# Enclosure_100x68_BHWL.net
KiCad netlist of a schematic drawn in EAGLE
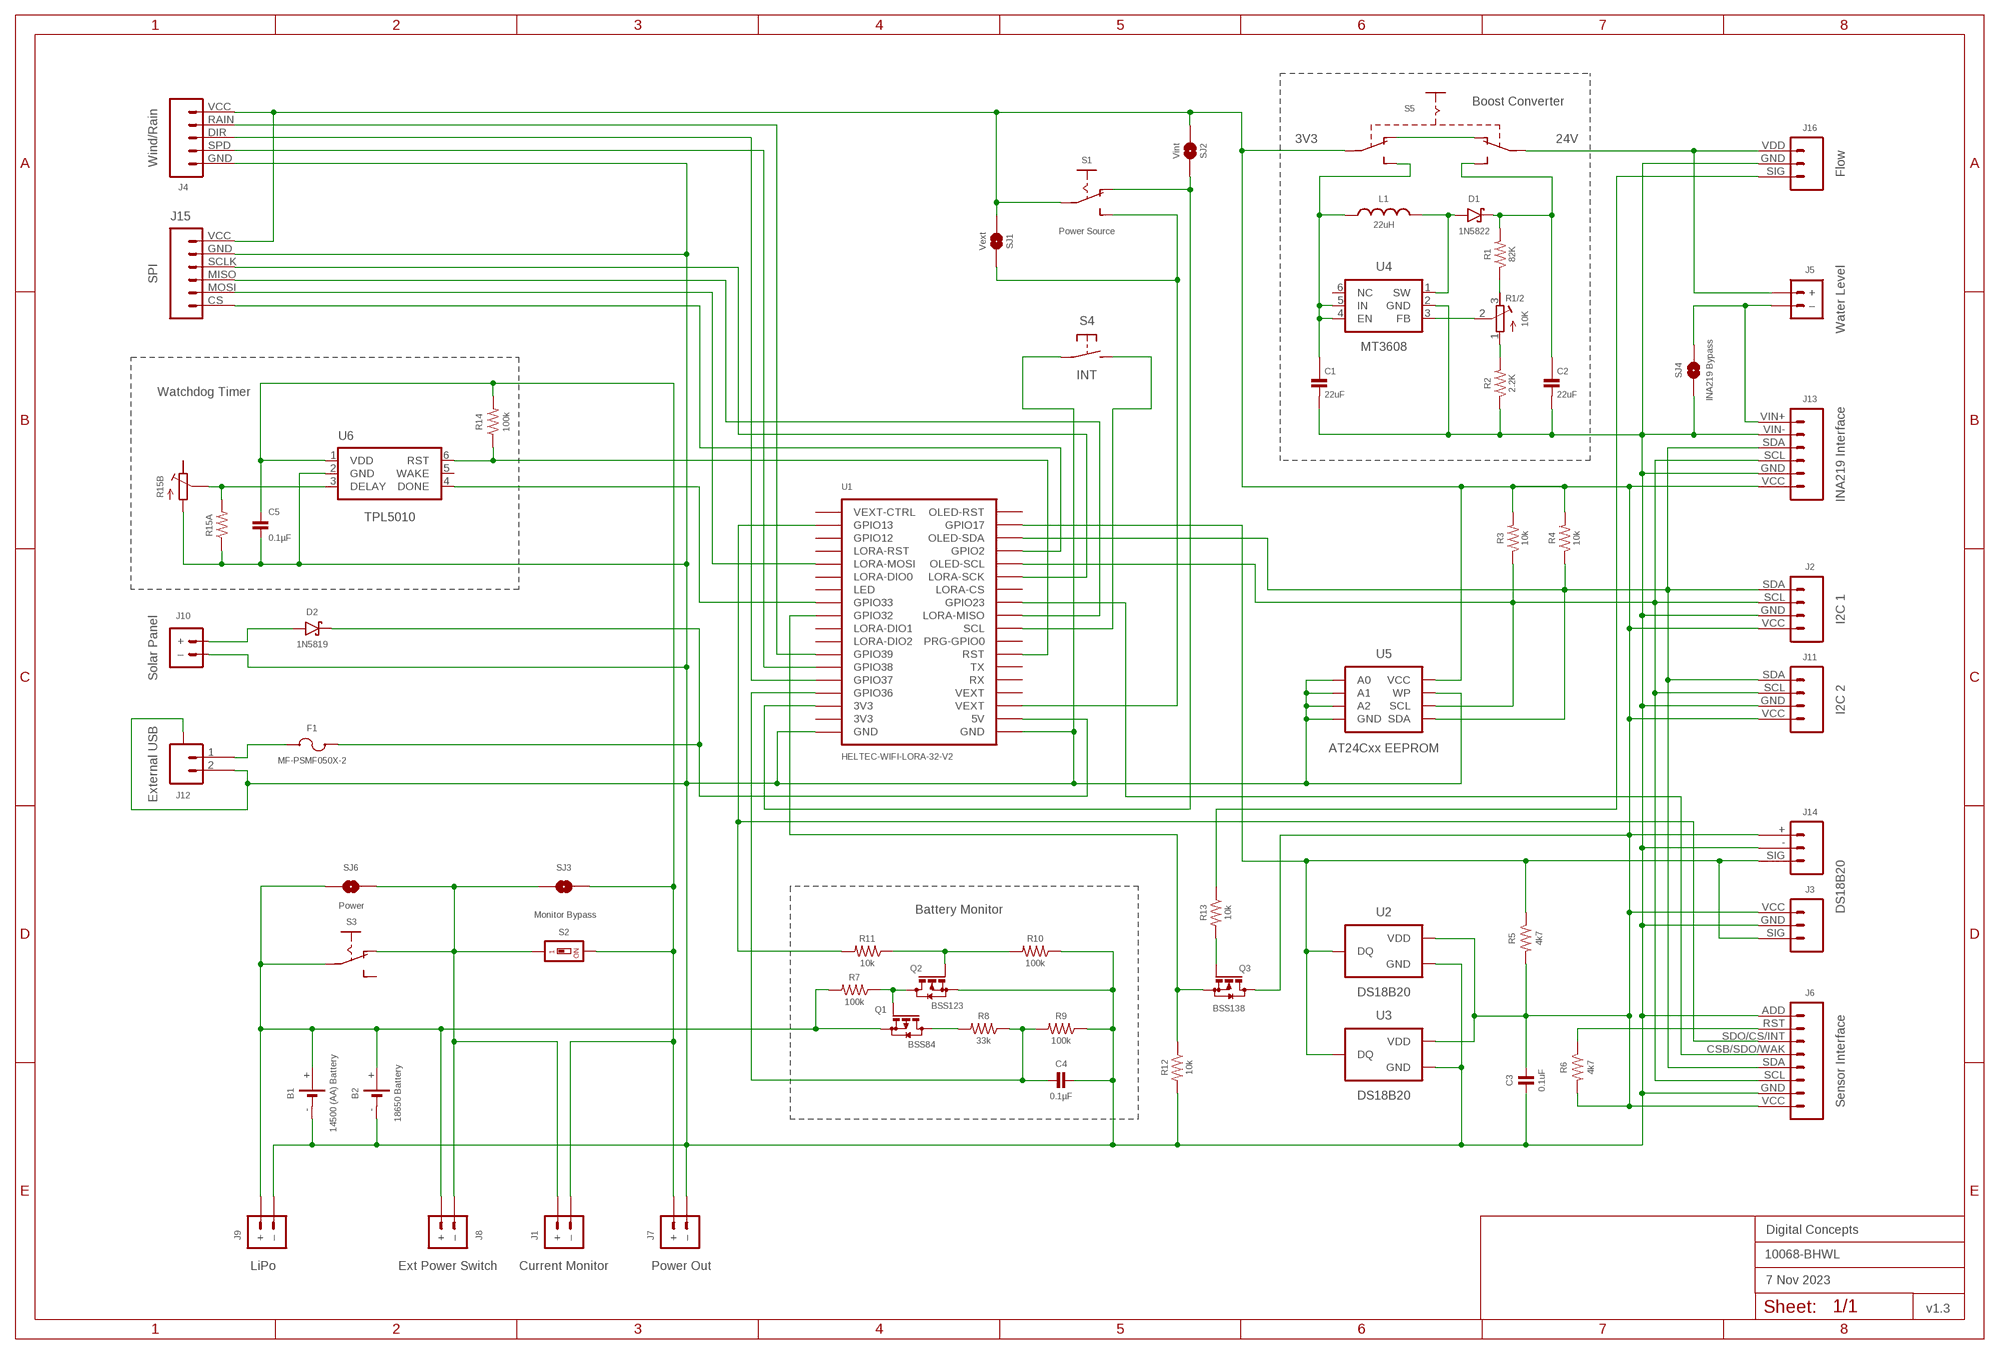
[diagram p0: schematic, sheet 1]

(export (version "E")
  (design (tool "Eeschema 10.0.6"))
  (components
    (comp (ref "B1")
      (value "14500 (AA) Battery")
      (footprint "eagle-import:BATTERY-14500")
      (libsource (lib "eagle-import") (part "BATTERY-HOLDER-14500(AA)"))
    )
    (comp (ref "B2")
      (value "18650 Battery")
      (footprint "eagle-import:BATTERY-18650")
      (libsource (lib "eagle-import") (part "BATTERY-HOLDER-18650"))
    )
    (comp (ref "C1")
      (value "22uF")
      (footprint "eagle-import:C1206")
      (libsource (lib "eagle-import") (part "CAPACITOR-1206"))
    )
    (comp (ref "C2")
      (value "22uF")
      (footprint "eagle-import:C1206")
      (libsource (lib "eagle-import") (part "CAPACITOR-1206"))
    )
    (comp (ref "C3")
      (value "0.1uF")
      (footprint "eagle-import:C0805")
      (libsource (lib "eagle-import") (part "CAPACITOR-0805"))
    )
    (comp (ref "C4")
      (value "0.1µF")
      (footprint "eagle-import:C0805")
      (libsource (lib "eagle-import") (part "CAPACITOR-0805"))
    )
    (comp (ref "C5")
      (value "0.1µF")
      (footprint "eagle-import:C0805")
      (libsource (lib "eagle-import") (part "CAPACITOR-0805"))
    )
    (comp (ref "D1")
      (value "1N5822")
      (footprint "eagle-import:DIODE_SMB")
      (libsource (lib "eagle-import") (part "DIODE-SCHOTTKY-1N5822"))
    )
    (comp (ref "D2")
      (value "1N5819")
      (footprint "eagle-import:SOD-123")
      (libsource (lib "eagle-import") (part "1N5819-SOD-123"))
    )
    (comp (ref "F1")
      (value "MF-PSMF050X-2")
      (footprint "eagle-import:F0805")
      (libsource (lib "eagle-import") (part "MF-PSMF050X-2"))
    )
    (comp (ref "J1")
      (value "Current Monitor")
      (footprint "eagle-import:JST-PH2.0-2-HORIZONTAL")
      (libsource (lib "eagle-import") (part "JST-PH2.0-2-HORIZONTALJST-PTH-2"))
    )
    (comp (ref "J2")
      (value "I2C 1")
      (footprint "eagle-import:JST-PH2.0-4-VERTICAL-I2C")
      (libsource (lib "eagle-import") (part "JST-PH2.0-4-VERTICAL-I2C"))
    )
    (comp (ref "J3")
      (value "DS18B20")
      (footprint "eagle-import:JST-PH2.0-3-VERTICAL-SIG")
      (libsource (lib "eagle-import") (part "JST-PH2.0-3-VERTICAL-DS18B20"))
    )
    (comp (ref "J4")
      (value "Wind/Rain")
      (footprint "eagle-import:JST-PH2.0-5-DUAL-WEATHER")
      (libsource (lib "eagle-import") (part "JST-PH2.0-5-DUAL-WEATHER"))
    )
    (comp (ref "J5")
      (value "Water Level")
      (footprint "eagle-import:JST-PH2.0-2-DUAL-POWER")
      (libsource (lib "eagle-import") (part "JST-PH2.0-2-DUAL-POWERJST-PTH-2"))
    )
    (comp (ref "J6")
      (value "Sensor Interface")
      (footprint "eagle-import:CONN_08-SENSOR")
      (libsource (lib "eagle-import") (part "HEADER-1X8-SENSOR"))
    )
    (comp (ref "J7")
      (value "Power Out")
      (footprint "eagle-import:JST-GH1.25-2-HORIZONTAL")
      (libsource (lib "eagle-import") (part "JST-GH1.25-2-HORIZONTAL-POWER"))
    )
    (comp (ref "J8")
      (value "Ext Power Switch")
      (footprint "eagle-import:JST-PH2.0-2-DUAL-POWER")
      (libsource (lib "eagle-import") (part "JST-PH2.0-2-DUAL-POWERJST-PTH-2"))
    )
    (comp (ref "J9")
      (value "LiPo")
      (footprint "eagle-import:JST-PH2.0-2-HORIZONTAL-POWER")
      (libsource (lib "eagle-import") (part "JST-PH2.0-2-HORIZONTAL-POWERJST-PTH-2"))
    )
    (comp (ref "J10")
      (value "Solar Panel")
      (footprint "eagle-import:JST-PH2.0-2-VERTICAL=POWER")
      (libsource (lib "eagle-import") (part "JST-PH2.0-2-VERTICAL"))
    )
    (comp (ref "J11")
      (value "I2C 2")
      (footprint "eagle-import:JST-PH2.0-4-HORIZONTAL")
      (libsource (lib "eagle-import") (part "JST-PH2.0-I2C-MALE-HORIZONTAL"))
    )
    (comp (ref "J12")
      (value "External USB")
      (footprint "eagle-import:JST-SH1.0-2-HORIZONTAL")
      (libsource (lib "eagle-import") (part "JST-SH1.0-2-SMD-HORIZONTAL"))
    )
    (comp (ref "J13")
      (value "INA219 Interface")
      (footprint "eagle-import:CONN_06-INA219")
      (libsource (lib "eagle-import") (part "INA219-I2C-MODULE"))
    )
    (comp (ref "J14")
      (value "JST-PH2.0-3-HORIZONTAL-DS18B20")
      (footprint "eagle-import:JST-PH2.0-3-HORIZONTAL-DS18B20")
      (libsource (lib "eagle-import") (part "JST-PH2.0-3-HORIZONTAL-DS18B20"))
    )
    (comp (ref "J15")
      (value "SPI")
      (footprint "eagle-import:JST-PH2.0-6-HORIZONTAL-SPI")
      (libsource (lib "eagle-import") (part "JST-PH2.0-6-HORIZONTAL-SPI"))
    )
    (comp (ref "J16")
      (value "Flow")
      (footprint "eagle-import:JST-XH2.4-3-VERTICAL-SENSOR")
      (libsource (lib "eagle-import") (part "JST-XH2.54-3-VERTICAL-SENSOR"))
    )
    (comp (ref "L1")
      (value "22uH")
      (footprint "eagle-import:CDRH104R+6D28")
      (libsource (lib "eagle-import") (part "INDUCTOR-CDRH104R/6D28L5038P"))
    )
    (comp (ref "Q1")
      (value "BSS84")
      (footprint "eagle-import:SOT23-3")
      (libsource (lib "eagle-import") (part "BSS84"))
    )
    (comp (ref "Q2")
      (value "BSS123")
      (footprint "eagle-import:SOT23-3")
      (libsource (lib "eagle-import") (part "MOSFET-BSS123"))
    )
    (comp (ref "Q3")
      (value "BSS138")
      (footprint "eagle-import:SOT23-3")
      (libsource (lib "eagle-import") (part "MOSFET-BSS123"))
    )
    (comp (ref "R1")
      (value "82K")
      (footprint "eagle-import:R0805")
      (libsource (lib "eagle-import") (part "RESISTORR0805"))
    )
    (comp (ref "R1/2")
      (value "10K")
      (footprint "eagle-import:RTRIM64P")
      (libsource (lib "eagle-import") (part "RESISTOR-TRIMM-BAOTER-HORIZONTAL"))
    )
    (comp (ref "R2")
      (value "2.2K")
      (footprint "eagle-import:R0805")
      (libsource (lib "eagle-import") (part "RESISTORR0805"))
    )
    (comp (ref "R3")
      (value "10k")
      (footprint "eagle-import:R0805")
      (libsource (lib "eagle-import") (part "RESISTORR0805"))
    )
    (comp (ref "R4")
      (value "10k")
      (footprint "eagle-import:R0805")
      (libsource (lib "eagle-import") (part "RESISTORR0805"))
    )
    (comp (ref "R5")
      (value "4k7")
      (footprint "eagle-import:R0805")
      (libsource (lib "eagle-import") (part "RESISTORR0805"))
    )
    (comp (ref "R6")
      (value "4k7")
      (footprint "eagle-import:R0805")
      (libsource (lib "eagle-import") (part "RESISTORR0805"))
    )
    (comp (ref "R7")
      (value "100k")
      (footprint "eagle-import:R0805")
      (libsource (lib "eagle-import") (part "RESISTORR0805"))
    )
    (comp (ref "R8")
      (value "33k")
      (footprint "eagle-import:R0805")
      (libsource (lib "eagle-import") (part "RESISTORR0805"))
    )
    (comp (ref "R9")
      (value "100k")
      (footprint "eagle-import:R0805")
      (libsource (lib "eagle-import") (part "RESISTORR0805"))
    )
    (comp (ref "R10")
      (value "100k")
      (footprint "eagle-import:R0805")
      (libsource (lib "eagle-import") (part "RESISTORR0805"))
    )
    (comp (ref "R11")
      (value "10k")
      (footprint "eagle-import:R0805")
      (libsource (lib "eagle-import") (part "RESISTORR0805"))
    )
    (comp (ref "R12")
      (value "10k")
      (footprint "eagle-import:R0805")
      (libsource (lib "eagle-import") (part "RESISTORR0805"))
    )
    (comp (ref "R13")
      (value "10k")
      (footprint "eagle-import:R0805")
      (libsource (lib "eagle-import") (part "RESISTORR0805"))
    )
    (comp (ref "R14")
      (value "100k")
      (footprint "eagle-import:R0805")
      (libsource (lib "eagle-import") (part "RESISTORR0805"))
    )
    (comp (ref "R15A")
      (value "RESISTORR0805")
      (footprint "eagle-import:R0805")
      (libsource (lib "eagle-import") (part "RESISTORR0805"))
    )
    (comp (ref "R15B")
      (value "RESISTOR-TRIMM-33")
      (footprint "eagle-import:RTRIM3_3")
      (libsource (lib "eagle-import") (part "RESISTOR-TRIMM-33"))
    )
    (comp (ref "S1")
      (value "Power Source")
      (footprint "eagle-import:SWITCH-SPDT-SMT")
      (libsource (lib "eagle-import") (part "SWITCH-SLIDE-SPDT-SMT"))
    )
    (comp (ref "S2")
      (value "Monitor Bypass")
      (footprint "eagle-import:SMD-001")
      (libsource (lib "eagle-import") (part "SWITCH-DIP-SWS001"))
    )
    (comp (ref "S3")
      (value "Power")
      (footprint "eagle-import:SWITCH-SPDT-PTH")
      (libsource (lib "eagle-import") (part "SWITCH-SLIDE-SPDT-PTH"))
    )
    (comp (ref "S4")
      (value "INT")
      (footprint "eagle-import:SWITCH-2-PAD")
      (libsource (lib "eagle-import") (part "SWITCH-MOMENTARY-2-PIN"))
    )
    (comp (ref "S5")
      (value "SWITCH-SLIDE-DPDT-PTH-S")
      (footprint "eagle-import:SWITCH-DPDT-PTH")
      (libsource (lib "eagle-import") (part "SWITCH-SLIDE-DPDT-PTH-S"))
    )
    (comp (ref "SJ1")
      (value "Vext")
      (footprint "eagle-import:SJ")
      (libsource (lib "eagle-import") (part "SJ"))
    )
    (comp (ref "SJ2")
      (value "Vint")
      (footprint "eagle-import:SJ-VIA-2")
      (libsource (lib "eagle-import") (part "SJ-V-2"))
    )
    (comp (ref "SJ3")
      (value "Monitor")
      (footprint "eagle-import:SJ")
      (libsource (lib "eagle-import") (part "SJ"))
    )
    (comp (ref "SJ4")
      (value "INA219 Bypass")
      (footprint "eagle-import:SJ")
      (libsource (lib "eagle-import") (part "SJ"))
    )
    (comp (ref "SJ6")
      (value "Power")
      (footprint "eagle-import:SJ")
      (libsource (lib "eagle-import") (part "SJ"))
    )
    (comp (ref "U1")
      (value "HELTEC-WIFI-LORA-32-V2")
      (footprint "eagle-import:HELTEC-WIFI-LORA-32-V2")
      (libsource (lib "eagle-import") (part "HELTEC-WIFI-LORA-32-V2"))
    )
    (comp (ref "U2")
      (value "DS18B20")
      (footprint "eagle-import:TO-92")
      (fields (field (name "MF") "Maxim Integrated"))
      (libsource (lib "eagle-import") (part "THERMOMETER-DS18B20"))
    )
    (comp (ref "U3")
      (value "DS18B20")
      (footprint "eagle-import:TO-92")
      (fields (field (name "MF") "Maxim Integrated"))
      (libsource (lib "eagle-import") (part "THERMOMETER-DS18B20"))
    )
    (comp (ref "U4")
      (value "MT3608")
      (footprint "eagle-import:SOT-23-6@1")
      (libsource (lib "eagle-import") (part "MT3608"))
    )
    (comp (ref "U5")
      (value "AT24Cxx EEPROM")
      (footprint "eagle-import:SOP-8")
      (libsource (lib "eagle-import") (part "AT24CXX-EEPROM"))
    )
    (comp (ref "U6")
      (value "TPL5010")
      (footprint "eagle-import:SOT-23-6")
      (libsource (lib "eagle-import") (part "TPL5010DDCR"))
    )
  )
  (nets
    (net (code "1") (name "Net-(C4-Pad1)") (class "Default")
      (node (ref "C4") (pin "1") (pinfunction "1_1") (pintype "passive"))
      (node (ref "R8") (pin "1") (pinfunction "1_1") (pintype "passive"))
      (node (ref "R9") (pin "2") (pinfunction "2_2") (pintype "passive"))
      (node (ref "U1") (pin "GPIO36") (pinfunction "GPIO36_GPIO36") (pintype "bidirectional"))
    )
    (net (code "2") (name "Net-(D2-PadA)") (class "Default")
      (node (ref "D2") (pin "A") (pinfunction "A_A") (pintype "passive"))
      (node (ref "J10") (pin "+") (pinfunction "+_+") (pintype "power_in"))
    )
    (net (code "3") (name "Net-(D2-PadC)") (class "Default")
      (node (ref "D2") (pin "C") (pinfunction "C_C") (pintype "passive"))
      (node (ref "F1") (pin "1") (pinfunction "1_1") (pintype "passive"))
      (node (ref "U1") (pin "5V") (pinfunction "5V_5V") (pintype "bidirectional"))
    )
    (net (code "4") (name "Net-(F1-Pad2)") (class "Default")
      (node (ref "F1") (pin "2") (pinfunction "2_2") (pintype "passive"))
      (node (ref "J12") (pin "1") (pinfunction "1_1") (pintype "passive"))
    )
    (net (code "5") (name "Net-(J1-+)") (class "Default")
      (node (ref "J1") (pin "1") (pinfunction "+_1") (pintype "power_in"))
      (node (ref "J8") (pin "-") (pinfunction "–_-") (pintype "power_in"))
      (node (ref "S2") (pin "1") (pinfunction "1_1") (pintype "passive"))
      (node (ref "S3") (pin "1") (pinfunction "O_1") (pintype "passive"))
      (node (ref "SJ3") (pin "2") (pinfunction "2_2") (pintype "passive"))
      (node (ref "SJ6") (pin "1") (pinfunction "1_1") (pintype "passive"))
    )
    (net (code "6") (name "Net-(J1-–)") (class "Default")
      (node (ref "C5") (pin "1") (pinfunction "1_1") (pintype "passive"))
      (node (ref "J1") (pin "2") (pinfunction "–_2") (pintype "power_in"))
      (node (ref "J7") (pin "+") (pinfunction "+_+") (pintype "power_in"))
      (node (ref "R14") (pin "2") (pinfunction "2_2") (pintype "passive"))
      (node (ref "S2") (pin "2") (pinfunction "2_2") (pintype "passive"))
      (node (ref "SJ3") (pin "1") (pinfunction "1_1") (pintype "passive"))
      (node (ref "U6") (pin "1") (pinfunction "VDD_1") (pintype "power_in"))
    )
    (net (code "7") (name "Net-(J4-2)") (class "Default")
      (node (ref "J4") (pin "RAIN") (pinfunction "2_RAIN") (pintype "passive"))
      (node (ref "U1") (pin "GPIO39") (pinfunction "GPIO39_GPIO39") (pintype "bidirectional"))
    )
    (net (code "8") (name "Net-(J4-3)") (class "Default")
      (node (ref "J4") (pin "DIR") (pinfunction "3_DIR") (pintype "passive"))
      (node (ref "U1") (pin "GPIO37") (pinfunction "GPIO37_GPIO37") (pintype "bidirectional"))
    )
    (net (code "9") (name "Net-(J4-4)") (class "Default")
      (node (ref "J4") (pin "SPD") (pinfunction "4_SPD") (pintype "passive"))
      (node (ref "U1") (pin "GPIO38") (pinfunction "GPIO38_GPIO38") (pintype "bidirectional"))
    )
    (net (code "10") (name "Net-(J6-5)") (class "Default")
      (node (ref "J6") (pin "CSB/SDO/WAK") (pinfunction "5_CSB/SDO/WAK") (pintype "passive"))
      (node (ref "U1") (pin "GPIO23") (pinfunction "GPIO23_GPIO23") (pintype "bidirectional"))
    )
    (net (code "11") (name "Net-(J6-6)") (class "Default")
      (node (ref "J6") (pin "SDO/CS/INT") (pinfunction "6_SDO/CS/INT") (pintype "passive"))
      (node (ref "R11") (pin "2") (pinfunction "2_2") (pintype "passive"))
      (node (ref "U1") (pin "GPIO13") (pinfunction "GPIO13_GPIO13") (pintype "bidirectional"))
    )
    (net (code "12") (name "Net-(J6-7)") (class "Default")
      (node (ref "J6") (pin "RST") (pinfunction "7_RST") (pintype "passive"))
      (node (ref "R6") (pin "1") (pinfunction "1_1") (pintype "passive"))
    )
    (net (code "13") (name "Net-(J10-–)") (class "Default")
      (node (ref "B1") (pin "-") (pinfunction "-_-") (pintype "power_in"))
      (node (ref "B2") (pin "-") (pinfunction "-_-") (pintype "power_in"))
      (node (ref "C1") (pin "2") (pinfunction "2_2") (pintype "passive"))
      (node (ref "C2") (pin "2") (pinfunction "2_2") (pintype "passive"))
      (node (ref "C3") (pin "2") (pinfunction "2_2") (pintype "passive"))
      (node (ref "C4") (pin "2") (pinfunction "2_2") (pintype "passive"))
      (node (ref "C5") (pin "2") (pinfunction "2_2") (pintype "passive"))
      (node (ref "J10") (pin "-") (pinfunction "–_-") (pintype "power_in"))
      (node (ref "J11") (pin "GND") (pinfunction "2_GND") (pintype "passive"))
      (node (ref "J12") (pin "2") (pinfunction "2_2") (pintype "passive"))
      (node (ref "J12") (pin "A@1") (pinfunction "A_A@1") (pintype "power_in"))
      (node (ref "J12") (pin "A@2") (pinfunction "A_A@2") (pintype "power_in"))
      (node (ref "J13") (pin "GND") (pinfunction "2_GND") (pintype "passive"))
      (node (ref "J13") (pin "VIN-") (pinfunction "5_VIN-") (pintype "passive"))
      (node (ref "J14") (pin "-") (pinfunction "2_-") (pintype "passive"))
      (node (ref "J15") (pin "GND") (pinfunction "5_GND") (pintype "passive"))
      (node (ref "J16") (pin "GND") (pinfunction "2_GND") (pintype "passive"))
      (node (ref "J2") (pin "GND") (pinfunction "3_GND") (pintype "passive"))
      (node (ref "J3") (pin "GND") (pinfunction "2_GND") (pintype "passive"))
      (node (ref "J4") (pin "GND") (pinfunction "5_GND") (pintype "passive"))
      (node (ref "J6") (pin "ADD") (pinfunction "8_ADD") (pintype "passive"))
      (node (ref "J6") (pin "GND") (pinfunction "2_GND") (pintype "passive"))
      (node (ref "J7") (pin "-") (pinfunction "–_-") (pintype "power_in"))
      (node (ref "J9") (pin "-") (pinfunction "–_-") (pintype "power_in"))
      (node (ref "Q2") (pin "2") (pinfunction "S_2") (pintype "passive"))
      (node (ref "R10") (pin "1") (pinfunction "1_1") (pintype "passive"))
      (node (ref "R12") (pin "2") (pinfunction "2_2") (pintype "passive"))
      (node (ref "R15A") (pin "1") (pinfunction "1_1") (pintype "passive"))
      (node (ref "R15B") (pin "1") (pinfunction "A_1") (pintype "passive"))
      (node (ref "R2") (pin "1") (pinfunction "1_1") (pintype "passive"))
      (node (ref "R9") (pin "1") (pinfunction "1_1") (pintype "passive"))
      (node (ref "S4") (pin "P$1") (pinfunction "P_P$1") (pintype "passive"))
      (node (ref "SJ4") (pin "1") (pinfunction "1_1") (pintype "passive"))
      (node (ref "U1") (pin "GND@1") (pinfunction "GND_GND@1") (pintype "bidirectional"))
      (node (ref "U1") (pin "GND@36") (pinfunction "GND_GND@36") (pintype "bidirectional"))
      (node (ref "U2") (pin "1") (pinfunction "GND_1") (pintype "power_in"))
      (node (ref "U3") (pin "1") (pinfunction "GND_1") (pintype "power_in"))
      (node (ref "U4") (pin "2") (pinfunction "GND_2") (pintype "power_in"))
      (node (ref "U5") (pin "P$1") (pinfunction "A0_P$1") (pintype "bidirectional"))
      (node (ref "U5") (pin "P$2") (pinfunction "A1_P$2") (pintype "bidirectional"))
      (node (ref "U5") (pin "P$3") (pinfunction "A2_P$3") (pintype "bidirectional"))
      (node (ref "U5") (pin "P$4") (pinfunction "GND_P$4") (pintype "bidirectional"))
      (node (ref "U5") (pin "P$7") (pinfunction "WP_P$7") (pintype "bidirectional"))
      (node (ref "U6") (pin "2") (pinfunction "GND_2") (pintype "power_in"))
    )
    (net (code "14") (name "Net-(J11-1)") (class "Default")
      (node (ref "C3") (pin "1") (pinfunction "1_1") (pintype "passive"))
      (node (ref "J11") (pin "VCC") (pinfunction "1_VCC") (pintype "passive"))
      (node (ref "J13") (pin "VCC") (pinfunction "1_VCC") (pintype "passive"))
      (node (ref "J14") (pin "+") (pinfunction "3_+") (pintype "passive"))
      (node (ref "J15") (pin "VCC") (pinfunction "6_VCC") (pintype "passive"))
      (node (ref "J2") (pin "VCC") (pinfunction "4_VCC") (pintype "passive"))
      (node (ref "J3") (pin "VCC") (pinfunction "3_VCC") (pintype "passive"))
      (node (ref "J4") (pin "VCC") (pinfunction "1_VCC") (pintype "passive"))
      (node (ref "J6") (pin "VCC") (pinfunction "1_VCC") (pintype "passive"))
      (node (ref "Q3") (pin "3") (pinfunction "D_3") (pintype "passive"))
      (node (ref "R3") (pin "2") (pinfunction "2_2") (pintype "passive"))
      (node (ref "R4") (pin "2") (pinfunction "2_2") (pintype "passive"))
      (node (ref "R5") (pin "2") (pinfunction "2_2") (pintype "passive"))
      (node (ref "R6") (pin "2") (pinfunction "2_2") (pintype "passive"))
      (node (ref "S1") (pin "2") (pinfunction "P_2") (pintype "passive"))
      (node (ref "S5") (pin "P$5") (pinfunction "P2_P$5") (pintype "passive"))
      (node (ref "SJ1") (pin "2") (pinfunction "2_2") (pintype "passive"))
      (node (ref "SJ2") (pin "2") (pinfunction "2_2") (pintype "passive"))
      (node (ref "SJ2") (pin "2@V") (pinfunction "2_2@V") (pintype "passive"))
      (node (ref "U2") (pin "3") (pinfunction "VDD_3") (pintype "power_in"))
      (node (ref "U3") (pin "3") (pinfunction "VDD_3") (pintype "power_in"))
      (node (ref "U5") (pin "P$8") (pinfunction "VCC_P$8") (pintype "bidirectional"))
    )
    (net (code "15") (name "Net-(J11-3)") (class "Default")
      (node (ref "J11") (pin "SCL") (pinfunction "3_SCL") (pintype "passive"))
      (node (ref "J13") (pin "SCL") (pinfunction "3_SCL") (pintype "passive"))
      (node (ref "J2") (pin "SCL") (pinfunction "2_SCL") (pintype "passive"))
      (node (ref "J6") (pin "SCL") (pinfunction "3_SCL") (pintype "passive"))
      (node (ref "R3") (pin "1") (pinfunction "1_1") (pintype "passive"))
      (node (ref "U1") (pin "GPIO15") (pinfunction "OLED-SCL_GPIO15") (pintype "bidirectional"))
      (node (ref "U5") (pin "P$6") (pinfunction "SCL_P$6") (pintype "bidirectional"))
    )
    (net (code "16") (name "Net-(J11-4)") (class "Default")
      (node (ref "J11") (pin "SDA") (pinfunction "4_SDA") (pintype "passive"))
      (node (ref "J13") (pin "SDA") (pinfunction "4_SDA") (pintype "passive"))
      (node (ref "J2") (pin "SDA") (pinfunction "1_SDA") (pintype "passive"))
      (node (ref "J6") (pin "SDA") (pinfunction "4_SDA") (pintype "passive"))
      (node (ref "R4") (pin "1") (pinfunction "1_1") (pintype "passive"))
      (node (ref "U1") (pin "GPIO4") (pinfunction "OLED-SDA_GPIO4") (pintype "bidirectional"))
      (node (ref "U5") (pin "P$5") (pinfunction "SDA_P$5") (pintype "bidirectional"))
    )
    (net (code "17") (name "Net-(J13-6)") (class "Default")
      (node (ref "J13") (pin "VIN+") (pinfunction "6_VIN+") (pintype "passive"))
      (node (ref "J5") (pin "-") (pinfunction "–_-") (pintype "power_in"))
      (node (ref "SJ4") (pin "2") (pinfunction "2_2") (pintype "passive"))
    )
    (net (code "18") (name "Net-(J14-1)") (class "Default")
      (node (ref "J14") (pin "SIG") (pinfunction "1_SIG") (pintype "passive"))
      (node (ref "J3") (pin "SIG") (pinfunction "1_SIG") (pintype "passive"))
      (node (ref "R5") (pin "1") (pinfunction "1_1") (pintype "passive"))
      (node (ref "U1") (pin "GPIO17") (pinfunction "GPIO17_GPIO17") (pintype "bidirectional"))
      (node (ref "U2") (pin "2") (pinfunction "DQ_2") (pintype "bidirectional"))
      (node (ref "U3") (pin "2") (pinfunction "DQ_2") (pintype "bidirectional"))
    )
    (net (code "19") (name "Net-(J15-1)") (class "Default")
      (node (ref "J15") (pin "CS") (pinfunction "1_CS") (pintype "passive"))
      (node (ref "U1") (pin "GPIO2") (pinfunction "GPIO2_GPIO2") (pintype "bidirectional"))
    )
    (net (code "20") (name "Net-(J15-2)") (class "Default")
      (node (ref "J15") (pin "MOSI") (pinfunction "2_MOSI") (pintype "passive"))
      (node (ref "U1") (pin "GPIO27") (pinfunction "LORA-MOSI_GPIO27") (pintype "bidirectional"))
    )
    (net (code "21") (name "Net-(J15-3)") (class "Default")
      (node (ref "J15") (pin "MISO") (pinfunction "3_MISO") (pintype "passive"))
      (node (ref "U1") (pin "GPIO19") (pinfunction "LORA-MISO_GPIO19") (pintype "bidirectional"))
    )
    (net (code "22") (name "Net-(J15-4)") (class "Default")
      (node (ref "J15") (pin "SCLK") (pinfunction "4_SCLK") (pintype "passive"))
      (node (ref "U1") (pin "GPIO5") (pinfunction "LORA-SCK_GPIO5") (pintype "bidirectional"))
    )
    (net (code "23") (name "Net-(J16-1)") (class "Default")
      (node (ref "J16") (pin "SIG") (pinfunction "1_SIG") (pintype "passive"))
      (node (ref "R13") (pin "1") (pinfunction "1_1") (pintype "passive"))
    )
    (net (code "24") (name "Net-(J16-3)") (class "Default")
      (node (ref "J16") (pin "VDD") (pinfunction "3_VDD") (pintype "passive"))
      (node (ref "J5") (pin "+") (pinfunction "+_+") (pintype "power_in"))
      (node (ref "S5") (pin "P$2") (pinfunction "P1_P$2") (pintype "passive"))
    )
    (net (code "25") (name "Net-(Q1-D)") (class "Default")
      (node (ref "Q1") (pin "3") (pinfunction "D_3") (pintype "passive"))
      (node (ref "R8") (pin "2") (pinfunction "2_2") (pintype "passive"))
    )
    (net (code "26") (name "Net-(Q1-G)") (class "Default")
      (node (ref "Q1") (pin "1") (pinfunction "G_1") (pintype "passive"))
      (node (ref "Q2") (pin "3") (pinfunction "D_3") (pintype "passive"))
      (node (ref "R7") (pin "1") (pinfunction "1_1") (pintype "passive"))
    )
    (net (code "27") (name "Net-(Q1-S)") (class "Default")
      (node (ref "B1") (pin "+") (pinfunction "+_+") (pintype "power_in"))
      (node (ref "B2") (pin "+") (pinfunction "+_+") (pintype "power_in"))
      (node (ref "J8") (pin "+") (pinfunction "+_+") (pintype "power_in"))
      (node (ref "J9") (pin "+") (pinfunction "+_+") (pintype "power_in"))
      (node (ref "Q1") (pin "2") (pinfunction "S_2") (pintype "passive"))
      (node (ref "R7") (pin "2") (pinfunction "2_2") (pintype "passive"))
      (node (ref "S3") (pin "2") (pinfunction "P_2") (pintype "passive"))
      (node (ref "SJ6") (pin "2") (pinfunction "2_2") (pintype "passive"))
    )
    (net (code "28") (name "Net-(Q2-G)") (class "Default")
      (node (ref "Q2") (pin "1") (pinfunction "G_1") (pintype "passive"))
      (node (ref "R10") (pin "2") (pinfunction "2_2") (pintype "passive"))
      (node (ref "R11") (pin "1") (pinfunction "1_1") (pintype "passive"))
    )
    (net (code "29") (name "Net-(Q3-G)") (class "Default")
      (node (ref "Q3") (pin "1") (pinfunction "G_1") (pintype "passive"))
      (node (ref "R13") (pin "2") (pinfunction "2_2") (pintype "passive"))
    )
    (net (code "30") (name "Net-(Q3-S)") (class "Default")
      (node (ref "Q3") (pin "2") (pinfunction "S_2") (pintype "passive"))
      (node (ref "R12") (pin "1") (pinfunction "1_1") (pintype "passive"))
      (node (ref "U1") (pin "GPIO32") (pinfunction "GPIO32_GPIO32") (pintype "bidirectional"))
    )
    (net (code "31") (name "Net-(R1/2-A)") (class "Default")
      (node (ref "R1/2") (pin "1") (pinfunction "A_1") (pintype "passive"))
      (node (ref "R2") (pin "2") (pinfunction "2_2") (pintype "passive"))
    )
    (net (code "32") (name "Net-(R1/2-E)") (class "Default")
      (node (ref "R1") (pin "1") (pinfunction "1_1") (pintype "passive"))
      (node (ref "R1/2") (pin "3") (pinfunction "E_3") (pintype "passive"))
    )
    (net (code "33") (name "Net-(R1/2-S)") (class "Default")
      (node (ref "R1/2") (pin "2") (pinfunction "S_2") (pintype "passive"))
      (node (ref "U4") (pin "3") (pinfunction "FB_3") (pintype "input"))
    )
    (net (code "34") (name "Net-(R15B-S)") (class "Default")
      (node (ref "R15A") (pin "2") (pinfunction "2_2") (pintype "passive"))
      (node (ref "R15B") (pin "2") (pinfunction "S_2") (pintype "passive"))
      (node (ref "U6") (pin "3") (pinfunction "DELAY_3") (pintype "input"))
    )
    (net (code "35") (name "Net-(S1-O)") (class "Default")
      (node (ref "S1") (pin "1") (pinfunction "O_1") (pintype "passive"))
      (node (ref "SJ2") (pin "1") (pinfunction "1_1") (pintype "passive"))
      (node (ref "U1") (pin "3V3@34") (pinfunction "3V3_3V3@34") (pintype "bidirectional"))
    )
    (net (code "36") (name "Net-(S1-S)") (class "Default")
      (node (ref "S1") (pin "3") (pinfunction "S_3") (pintype "passive"))
      (node (ref "SJ1") (pin "1") (pinfunction "1_1") (pintype "passive"))
      (node (ref "U1") (pin "VEXT@3") (pinfunction "VEXT_VEXT@3") (pintype "bidirectional"))
    )
    (net (code "37") (name "Net-(S4-S)") (class "Default")
      (node (ref "S4") (pin "P$2") (pinfunction "S_P$2") (pintype "passive"))
      (node (ref "U1") (pin "GPIO22") (pinfunction "SCL_GPIO22") (pintype "bidirectional"))
    )
    (net (code "38") (name "Net-(S5-O1)") (class "Default")
      (node (ref "S5") (pin "P$1") (pinfunction "O1_P$1") (pintype "passive"))
      (node (ref "S5") (pin "P$4") (pinfunction "O2_P$4") (pintype "passive"))
    )
    (net (code "39") (name "Net-(S5-S1)") (class "Default")
      (node (ref "C2") (pin "1") (pinfunction "1_1") (pintype "passive"))
      (node (ref "D1") (pin "C") (pinfunction "C_C") (pintype "passive"))
      (node (ref "R1") (pin "2") (pinfunction "2_2") (pintype "passive"))
      (node (ref "S5") (pin "P$3") (pinfunction "S1_P$3") (pintype "passive"))
    )
    (net (code "40") (name "Net-(S5-S2)") (class "Default")
      (node (ref "C1") (pin "1") (pinfunction "1_1") (pintype "passive"))
      (node (ref "L1") (pin "2") (pinfunction "2_2") (pintype "passive"))
      (node (ref "S5") (pin "P$6") (pinfunction "S2_P$6") (pintype "passive"))
      (node (ref "U4") (pin "4") (pinfunction "EN_4") (pintype "input"))
      (node (ref "U4") (pin "5") (pinfunction "IN_5") (pintype "power_in"))
    )
    (net (code "41") (name "Net-(U4-SW)") (class "Default")
      (node (ref "D1") (pin "A") (pinfunction "A_A") (pintype "passive"))
      (node (ref "L1") (pin "1") (pinfunction "1_1") (pintype "passive"))
      (node (ref "U4") (pin "1") (pinfunction "SW_1") (pintype "power_in"))
    )
    (net (code "42") (name "Net-(U6-DONE)") (class "Default")
      (node (ref "U1") (pin "GPIO33") (pinfunction "GPIO33_GPIO33") (pintype "bidirectional"))
      (node (ref "U6") (pin "4") (pinfunction "DONE_4") (pintype "input"))
    )
    (net (code "43") (name "Net-(U6-RST)") (class "Default")
      (node (ref "R14") (pin "1") (pinfunction "1_1") (pintype "passive"))
      (node (ref "U1") (pin "RST") (pinfunction "RST_RST") (pintype "bidirectional"))
      (node (ref "U6") (pin "6") (pinfunction "RST_6") (pintype "output"))
    )
    (net (code "44") (name "unconnected-(R15B-E-Pad3)") (class "Default")
      (node (ref "R15B") (pin "3") (pinfunction "E_3") (pintype "passive"))
    )
    (net (code "45") (name "unconnected-(S3-S-Pad3)") (class "Default")
      (node (ref "S3") (pin "3") (pinfunction "S_3") (pintype "passive"))
    )
    (net (code "46") (name "unconnected-(U1-3V3-Pad3V3@35)") (class "Default")
      (node (ref "U1") (pin "3V3@35") (pinfunction "3V3_3V3@35") (pintype "bidirectional"))
    )
    (net (code "47") (name "unconnected-(U1-LED-PadGPIO25)") (class "Default")
      (node (ref "U1") (pin "GPIO25") (pinfunction "LED_GPIO25") (pintype "bidirectional"))
    )
    (net (code "48") (name "unconnected-(U1-LORA-CS-PadGPIO18)") (class "Default")
      (node (ref "U1") (pin "GPIO18") (pinfunction "LORA-CS_GPIO18") (pintype "bidirectional"))
    )
    (net (code "49") (name "unconnected-(U1-LORA-DIO0-PadGPIO26)") (class "Default")
      (node (ref "U1") (pin "GPIO26") (pinfunction "LORA-DIO0_GPIO26") (pintype "bidirectional"))
    )
    (net (code "50") (name "unconnected-(U1-LORA-DIO1-PadGPIO35)") (class "Default")
      (node (ref "U1") (pin "GPIO35") (pinfunction "LORA-DIO1_GPIO35") (pintype "bidirectional"))
    )
    (net (code "51") (name "unconnected-(U1-LORA-DIO2-PadGPIO34)") (class "Default")
      (node (ref "U1") (pin "GPIO34") (pinfunction "LORA-DIO2_GPIO34") (pintype "bidirectional"))
    )
    (net (code "52") (name "unconnected-(U1-LORA-RST-PadGPIO14)") (class "Default")
      (node (ref "U1") (pin "GPIO14") (pinfunction "LORA-RST_GPIO14") (pintype "bidirectional"))
    )
    (net (code "53") (name "unconnected-(U1-OLED-RST-PadGPIO16)") (class "Default")
      (node (ref "U1") (pin "GPIO16") (pinfunction "OLED-RST_GPIO16") (pintype "bidirectional"))
    )
    (net (code "54") (name "unconnected-(U1-PRG-GPIO0-PadGPIO0)") (class "Default")
      (node (ref "U1") (pin "GPIO0") (pinfunction "PRG-GPIO0_GPIO0") (pintype "bidirectional"))
    )
    (net (code "55") (name "unconnected-(U1-PadGPIO12)") (class "Default")
      (node (ref "U1") (pin "GPIO12") (pinfunction "GPIO12_GPIO12") (pintype "bidirectional"))
    )
    (net (code "56") (name "unconnected-(U1-PadRX)") (class "Default")
      (node (ref "U1") (pin "RX") (pinfunction "RX_RX") (pintype "bidirectional"))
    )
    (net (code "57") (name "unconnected-(U1-PadTX)") (class "Default")
      (node (ref "U1") (pin "TX") (pinfunction "TX_TX") (pintype "bidirectional"))
    )
    (net (code "58") (name "unconnected-(U1-VEXT-CTRL-PadGPIO21)") (class "Default")
      (node (ref "U1") (pin "GPIO21") (pinfunction "VEXT-CTRL_GPIO21") (pintype "bidirectional"))
    )
    (net (code "59") (name "unconnected-(U1-VEXT-PadVEXT@4)") (class "Default")
      (node (ref "U1") (pin "VEXT@4") (pinfunction "VEXT_VEXT@4") (pintype "bidirectional"))
    )
    (net (code "60") (name "unconnected-(U4-NC-Pad6)") (class "Default")
      (node (ref "U4") (pin "6") (pinfunction "NC_6") (pintype "no_connect"))
    )
    (net (code "61") (name "unconnected-(U6-WAKE-Pad5)") (class "Default")
      (node (ref "U6") (pin "5") (pinfunction "WAKE_5") (pintype "output"))
    )
  )
)
